# IR_LED.net
KiCad netlist of a schematic drawn in Altium Designer
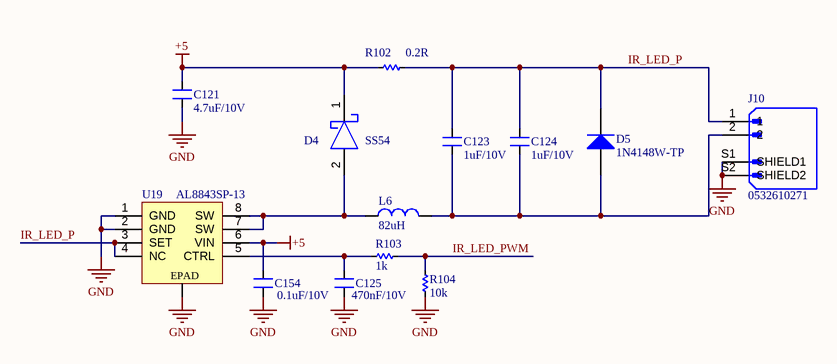
[diagram p0: IR_LED.SchDoc]

(export (version "E")
  (design (tool "Eeschema 10.0.6"))
  (components
    (comp (ref "C121")
      (value "4.7uF/10V")
      (footprint "CAP_C_1608X80")
      (libsource (lib "Sang_library") (part "Capacitors"))
    )
    (comp (ref "C123")
      (value "1uF/10V")
      (footprint "CAP_C_1608X80")
      (libsource (lib "Sang_library") (part "Capacitors"))
    )
    (comp (ref "C124")
      (value "1uF/10V")
      (footprint "CAP_C_1608X80")
      (libsource (lib "Sang_library") (part "Capacitors"))
    )
    (comp (ref "C125")
      (value "470nF/10V")
      (footprint "CAP_C_1608X80")
      (libsource (lib "Sang_library") (part "Capacitors"))
    )
    (comp (ref "C154")
      (value "0.1uF/10V")
      (footprint "CAP_C_1608X80")
      (libsource (lib "Sang_library") (part "Capacitors"))
    )
    (comp (ref "D4")
      (value "SS54")
      (footprint "DO214-AC-SMA_EXP_V110")
      (description "DIODE SCHOTTKY 40V 5A SMA")
      (libsource (lib "Sang_library") (part "B360B-E3/52T"))
    )
    (comp (ref "D5")
      (value "1N4148W-TP")
      (footprint "SOD-123-EXP-V110")
      (description "DIODE GEN PURP 100V 300MA SOD123")
      (fields (field (name "MPN") "1N4148W-7-F") (field (name "MFR") "Diodes Incorporated"))
      (libsource (lib "Sang_library") (part "1N4148-W-7"))
    )
    (comp (ref "J10")
      (value "0532610271")
      (footprint "0532610271")
      (description "CONN HEADER SMD R/A 2POS 1.25MM")
      (libsource (lib "EXP_HW_V2") (part "CONN_SMD_02"))
    )
    (comp (ref "L6")
      (value "82uH")
      (footprint "L-SMD-M-4.8x4.8x2.8mm")
      (description "SRR4828A-820M")
      (fields
        (field (name "PARTNO") "78477010")
        (field (name "MANUFACTURER") "Wurth Elektronik")
        (field (name "CREATED BY") "Baojun Chen")
      )
      (libsource (lib "Sang_library") (part "L-SMD-1"))
    )
    (comp (ref "R102")
      (value "0.2R")
      (footprint "RES_C_3216X70")
      (description "RES 0.2 OHM 1% 1W 1206")
      (fields
        (field (name "MANUFACTURER") "Generic Components")
        (field (name "PUBLISHER") "Altium Hobart Technology Centre")
      )
      (libsource (lib "Library") (part "Res-SMD"))
    )
    (comp (ref "R103")
      (value "1k")
      (footprint "RES_C_1608X60")
      (description "SMD")
      (fields
        (field (name "MANUFACTURER") "Generic Components")
        (field (name "PUBLISHER") "Altium Hobart Technology Centre")
      )
      (libsource (lib "Sang_library") (part "Res SMD"))
    )
    (comp (ref "R104")
      (value "10k")
      (footprint "RES_C_1608X60")
      (description "SMD")
      (fields
        (field (name "MANUFACTURER") "Generic Components")
        (field (name "PUBLISHER") "Altium Hobart Technology Centre")
      )
      (libsource (lib "Sang_library") (part "Res SMD"))
    )
    (comp (ref "U19")
      (value "AL8843SP-13")
      (footprint "SO8_EPAD")
      (description "IC LED DRIVER RGLTR PWM 3A 8SO")
      (libsource (lib "Sang_library") (part "AL8843SP-13"))
    )
  )
  (nets
    (net (code "1") (name "+5") (class "Default")
      (node (ref "C121") (pin "2") (pinfunction "2_2") (pintype "passive"))
      (node (ref "C154") (pin "2") (pinfunction "2_2") (pintype "passive"))
      (node (ref "D4") (pin "1") (pinfunction "1_1") (pintype "passive"))
      (node (ref "R102") (pin "2") (pinfunction "2_2") (pintype "passive"))
      (node (ref "U19") (pin "6") (pinfunction "VIN_6") (pintype "passive"))
    )
    (net (code "2") (name "/IR_LED_P") (class "Default")
      (node (ref "C123") (pin "2") (pinfunction "2_2") (pintype "passive"))
      (node (ref "C124") (pin "2") (pinfunction "2_2") (pintype "passive"))
      (node (ref "D5") (pin "2") (pinfunction "K_2") (pintype "passive"))
      (node (ref "J10") (pin "1") (pinfunction "1_1") (pintype "passive"))
      (node (ref "R102") (pin "1") (pinfunction "1_1") (pintype "passive"))
      (node (ref "U19") (pin "3") (pinfunction "SET_3") (pintype "passive"))
      (node (ref "U19") (pin "4") (pinfunction "NC_4") (pintype "passive"))
    )
    (net (code "3") (name "/IR_LED_PWM") (class "Default")
      (node (ref "R103") (pin "2") (pinfunction "2_2") (pintype "passive"))
      (node (ref "R104") (pin "2") (pinfunction "2_2") (pintype "passive"))
    )
    (net (code "4") (name "GND") (class "Default")
      (node (ref "C121") (pin "1") (pinfunction "1_1") (pintype "passive"))
      (node (ref "C125") (pin "1") (pinfunction "1_1") (pintype "passive"))
      (node (ref "C154") (pin "1") (pinfunction "1_1") (pintype "passive"))
      (node (ref "J10") (pin "S1") (pinfunction "SHIELD1_S1") (pintype "passive"))
      (node (ref "J10") (pin "S2") (pinfunction "SHIELD2_S2") (pintype "passive"))
      (node (ref "R104") (pin "1") (pinfunction "1_1") (pintype "passive"))
      (node (ref "U19") (pin "1") (pinfunction "GND_1") (pintype "passive"))
      (node (ref "U19") (pin "2") (pinfunction "GND_2") (pintype "passive"))
      (node (ref "U19") (pin "EPAD") (pinfunction "EPAD_EPAD") (pintype "passive"))
    )
    (net (code "5") (name "Net-(D4-Pad2)") (class "Default")
      (node (ref "D4") (pin "2") (pinfunction "2_2") (pintype "passive"))
      (node (ref "L6") (pin "1") (pinfunction "1_1") (pintype "passive"))
      (node (ref "U19") (pin "7") (pinfunction "SW_7") (pintype "passive"))
      (node (ref "U19") (pin "8") (pinfunction "SW_8") (pintype "passive"))
    )
    (net (code "6") (name "Net-(D5-A)") (class "Default")
      (node (ref "C123") (pin "1") (pinfunction "1_1") (pintype "passive"))
      (node (ref "C124") (pin "1") (pinfunction "1_1") (pintype "passive"))
      (node (ref "D5") (pin "1") (pinfunction "A_1") (pintype "passive"))
      (node (ref "J10") (pin "2") (pinfunction "2_2") (pintype "passive"))
      (node (ref "L6") (pin "2") (pinfunction "2_2") (pintype "passive"))
    )
    (net (code "7") (name "Net-(U19-CTRL)") (class "Default")
      (node (ref "C125") (pin "2") (pinfunction "2_2") (pintype "passive"))
      (node (ref "R103") (pin "1") (pinfunction "1_1") (pintype "passive"))
      (node (ref "U19") (pin "5") (pinfunction "CTRL_5") (pintype "passive"))
    )
  )
)
